# PowerSupply.net
KiCad netlist of a schematic drawn in Altium Designer
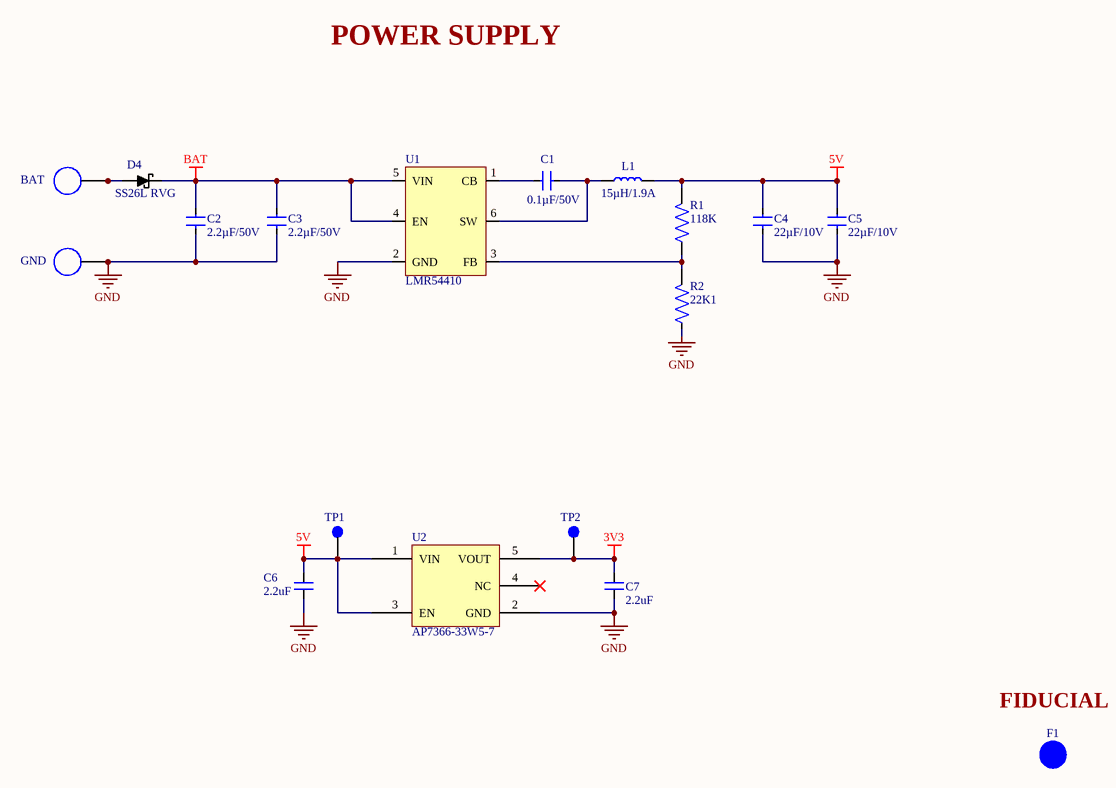
[diagram p0: PowerSupply.SchDoc]

(export (version "E")
  (design (tool "Eeschema 10.0.6"))
  (components
    (comp (ref "BAT")
      (value "Terminal")
      (footprint "2.5mmHOLE")
      (libsource (lib "Schlib1") (part "Terminal"))
    )
    (comp (ref "C1")
      (value "0.1µF/50V")
      (footprint "C0402")
      (description "MLCC - 0.1µF 50V  0402 X7R ±10%")
      (fields
        (field (name "TOLERANCE") "10%")
        (field (name "MANUFACTURER") "Murata")
        (field (name ".PCBCHECKED") "Alex Batista")
        (field (name ".SCHCHECKED") "Alex Batista")
      )
      (libsource (lib "Schlib1") (part "GRM155R71H104KE14J"))
    )
    (comp (ref "C2")
      (value "2.2µF/50V")
      (footprint "C0603")
      (description "MLCC - 2.2µF 50V  0603 X5R ±10%")
      (fields
        (field (name "TOLERANCE") "10%")
        (field (name "MANUFACTURER") "Murata")
        (field (name ".SCHCHECKED") "Alex Batista")
        (field (name ".PCBCHECKED") "Alex Batista")
      )
      (libsource (lib "Schlib1") (part "GRT188R61H225KE13D"))
    )
    (comp (ref "C3")
      (value "2.2µF/50V")
      (footprint "C0603")
      (description "MLCC - 2.2µF 50V  0603 X5R ±10%")
      (fields
        (field (name "TOLERANCE") "10%")
        (field (name "MANUFACTURER") "Murata")
        (field (name ".SCHCHECKED") "Alex Batista")
        (field (name ".PCBCHECKED") "Alex Batista")
      )
      (libsource (lib "Schlib1") (part "GRT188R61H225KE13D"))
    )
    (comp (ref "C4")
      (value "22µF/10V")
      (footprint "C0603")
      (description "MLCC - 22µF 10V 0603 X5R ±20%")
      (fields
        (field (name "MANUFACTURER") "Samsung")
        (field (name "MANUFACTURER PART NUMBER") "CL10A226MP8NUNE")
        (field (name ".SCHCHECKED") "Alex Batista")
        (field (name ".PCBCHECKED") "Alex Batista")
      )
      (libsource (lib "Schlib1") (part "CL10A226MP8NUNE"))
    )
    (comp (ref "C5")
      (value "22µF/10V")
      (footprint "C0603")
      (description "MLCC - 22µF 10V 0603 X5R ±20%")
      (fields
        (field (name "MANUFACTURER") "Samsung")
        (field (name "MANUFACTURER PART NUMBER") "CL10A226MP8NUNE")
        (field (name ".SCHCHECKED") "Alex Batista")
        (field (name ".PCBCHECKED") "Alex Batista")
      )
      (libsource (lib "Schlib1") (part "CL10A226MP8NUNE"))
    )
    (comp (ref "C6")
      (value "2.2uF")
      (footprint "C0603")
      (fields
        (field (name "MANUFACTURER") "KEMET")
        (field (name "MANUFACTURER PART NUMBER") "C0603C225K4PACTU")
        (field (name "TOLERANCE") "10%")
      )
      (libsource (lib "Schlib1") (part "C0603C225K4PACTU"))
    )
    (comp (ref "C7")
      (value "2.2uF")
      (footprint "C0603")
      (fields
        (field (name "MANUFACTURER") "KEMET")
        (field (name "MANUFACTURER PART NUMBER") "C0603C225K4PACTU")
        (field (name "TOLERANCE") "10%")
      )
      (libsource (lib "Schlib1") (part "C0603C225K4PACTU"))
    )
    (comp (ref "D4")
      (value "SS26L RVG")
      (footprint "SS26LRVG")
      (description "DIODE - Schottky 60V 2A 2-Pin Sub SMA T/R")
      (fields
        (field (name "MANUFACTURER") "Taiwan Semiconductor")
        (field (name ".SCHCHECKED") "Alex Batista")
        (field (name ".PCBCHECKED") "Alex Batista")
      )
      (libsource (lib "Schlib1") (part "SS26L RVG"))
    )
    (comp (ref "F1")
      (value "FIDUCIAL")
      (footprint "FID_40x120")
      (libsource (lib "Schlib1") (part "FIDUCIAL"))
    )
    (comp (ref "GND")
      (value "Terminal")
      (footprint "2.5mmHOLE")
      (libsource (lib "Schlib1") (part "Terminal"))
    )
    (comp (ref "L1")
      (value "15µH/1.9A")
      (footprint "SRN6045-150M")
      (description "IND - 15µH Semi-Shielded 1.9 A 95.8mOhm")
      (fields
        (field (name "TOLERANCE") "20%")
        (field (name "MANUFACTURER") "Bourns")
        (field (name ".SCHCHECKED") "Alex Batista")
        (field (name ".PCBCHECKED") "Alex Batista")
      )
      (libsource (lib "Schlib1") (part "SRN6045-150M"))
    )
    (comp (ref "R1")
      (value "118K")
      (footprint "R0402")
      (description "RES - 118K 1/16W 0402 ±1%")
      (fields
        (field (name "TOLERANCE") "1%")
        (field (name "MANUFACTURER") "Yageo")
        (field (name ".SCHCHECKED") "Alex Batista")
        (field (name ".PCBCHECKED") "Alex Batista")
      )
      (libsource (lib "Schlib1") (part "RC0402FR-07118KL"))
    )
    (comp (ref "R2")
      (value "22K1")
      (footprint "R0402")
      (description "RES - 22K1 1/16W 0402 ±1%")
      (fields
        (field (name "TOLERANCE") "1%")
        (field (name "MANUFACTURER") "Yageo")
        (field (name ".PCBCHECKED") "Alex Batista")
        (field (name ".SCHCHECKED") "Alex Batista")
      )
      (libsource (lib "Schlib1") (part "RC0402FR-0722K1L"))
    )
    (comp (ref "TP1")
      (value "TP")
      (footprint "TP")
      (description "Test Point")
      (libsource (lib "Schlib1") (part "TP"))
    )
    (comp (ref "TP2")
      (value "TP")
      (footprint "TP")
      (description "Test Point")
      (libsource (lib "Schlib1") (part "TP"))
    )
    (comp (ref "U1")
      (value "LMR54410")
      (footprint "LMR54410")
      (description "IC - DC/DC BUCK, Current-mode, 1A, 1100kHz SOT32-6")
      (fields
        (field (name "MANUFACTURER") "Texas Instruments")
        (field (name "MANUFACTURER PART NUMBER") "LMR54410DBVR")
        (field (name ".SCHCHECKED") "Alex Batista")
        (field (name ".PCBCHECKED") "Alex Batista")
      )
      (libsource (lib "Schlib1") (part "LMR54410DBVR"))
    )
    (comp (ref "U2")
      (value "AP7366-33W5-7")
      (footprint "SOT25")
      (description "Ldo, Fixed, 3.3V, 0.6A, -40 To 85Deg C Rohs Compliant: Yes ¦Diodes Inc. AP7366-33W5-7")
      (fields (field (name "MANUFACTURER") "Diodes"))
      (libsource (lib "Schlib1") (part "AP7366-33W5-7"))
    )
  )
  (nets
    (net (code "1") (name "3V3") (class "Default")
      (node (ref "C7") (pin "2") (pinfunction "2_2") (pintype "passive"))
      (node (ref "TP2") (pin "1") (pinfunction "1_1") (pintype "passive"))
      (node (ref "U2") (pin "5") (pinfunction "VOUT_5") (pintype "passive"))
    )
    (net (code "2") (name "5V") (class "Default")
      (node (ref "C4") (pin "2") (pinfunction "2_2") (pintype "passive"))
      (node (ref "C5") (pin "2") (pinfunction "2_2") (pintype "passive"))
      (node (ref "C6") (pin "2") (pinfunction "2_2") (pintype "passive"))
      (node (ref "L1") (pin "2") (pinfunction "2_2") (pintype "passive"))
      (node (ref "R1") (pin "2") (pinfunction "2_2") (pintype "passive"))
      (node (ref "TP1") (pin "1") (pinfunction "1_1") (pintype "passive"))
      (node (ref "U2") (pin "1") (pinfunction "VIN_1") (pintype "passive"))
      (node (ref "U2") (pin "3") (pinfunction "EN_3") (pintype "passive"))
    )
    (net (code "3") (name "BAT") (class "Default")
      (node (ref "C2") (pin "2") (pinfunction "2_2") (pintype "passive"))
      (node (ref "C3") (pin "2") (pinfunction "2_2") (pintype "passive"))
      (node (ref "D4") (pin "1") (pinfunction "Cathode_1") (pintype "passive"))
      (node (ref "U1") (pin "4") (pinfunction "EN_4") (pintype "passive"))
      (node (ref "U1") (pin "5") (pinfunction "VIN_5") (pintype "passive"))
    )
    (net (code "4") (name "GND") (class "Default")
      (node (ref "C2") (pin "1") (pinfunction "1_1") (pintype "passive"))
      (node (ref "C3") (pin "1") (pinfunction "1_1") (pintype "passive"))
      (node (ref "C4") (pin "1") (pinfunction "1_1") (pintype "passive"))
      (node (ref "C5") (pin "1") (pinfunction "1_1") (pintype "passive"))
      (node (ref "C6") (pin "1") (pinfunction "1_1") (pintype "passive"))
      (node (ref "C7") (pin "1") (pinfunction "1_1") (pintype "passive"))
      (node (ref "GND") (pin "1") (pinfunction "1_1") (pintype "passive"))
      (node (ref "R2") (pin "1") (pinfunction "1_1") (pintype "passive"))
      (node (ref "U1") (pin "2") (pinfunction "GND_2") (pintype "passive"))
      (node (ref "U2") (pin "2") (pinfunction "GND_2") (pintype "passive"))
    )
    (net (code "5") (name "Net-(D4-Anode)") (class "Default")
      (node (ref "BAT") (pin "1") (pinfunction "1_1") (pintype "passive"))
      (node (ref "D4") (pin "2") (pinfunction "Anode_2") (pintype "passive"))
    )
    (net (code "6") (name "Net-(U1-CB)") (class "Default")
      (node (ref "C1") (pin "1") (pinfunction "1_1") (pintype "passive"))
      (node (ref "U1") (pin "1") (pinfunction "CB_1") (pintype "passive"))
    )
    (net (code "7") (name "Net-(U1-FB)") (class "Default")
      (node (ref "R1") (pin "1") (pinfunction "1_1") (pintype "passive"))
      (node (ref "R2") (pin "2") (pinfunction "2_2") (pintype "passive"))
      (node (ref "U1") (pin "3") (pinfunction "FB_3") (pintype "passive"))
    )
    (net (code "8") (name "Net-(U1-SW)") (class "Default")
      (node (ref "C1") (pin "2") (pinfunction "2_2") (pintype "passive"))
      (node (ref "L1") (pin "1") (pinfunction "1_1") (pintype "passive"))
      (node (ref "U1") (pin "6") (pinfunction "SW_6") (pintype "passive"))
    )
    (net (code "9") (name "unconnected-(F1-Pad1)") (class "Default")
      (node (ref "F1") (pin "1") (pinfunction "1_1") (pintype "passive"))
    )
    (net (code "10") (name "unconnected-(U2-NC-Pad4)") (class "Default")
      (node (ref "U2") (pin "4") (pinfunction "NC_4") (pintype "passive+no_connect"))
    )
  )
)
